# SparkFun_tDof-TMF8820.net
KiCad netlist of a schematic drawn in EAGLE
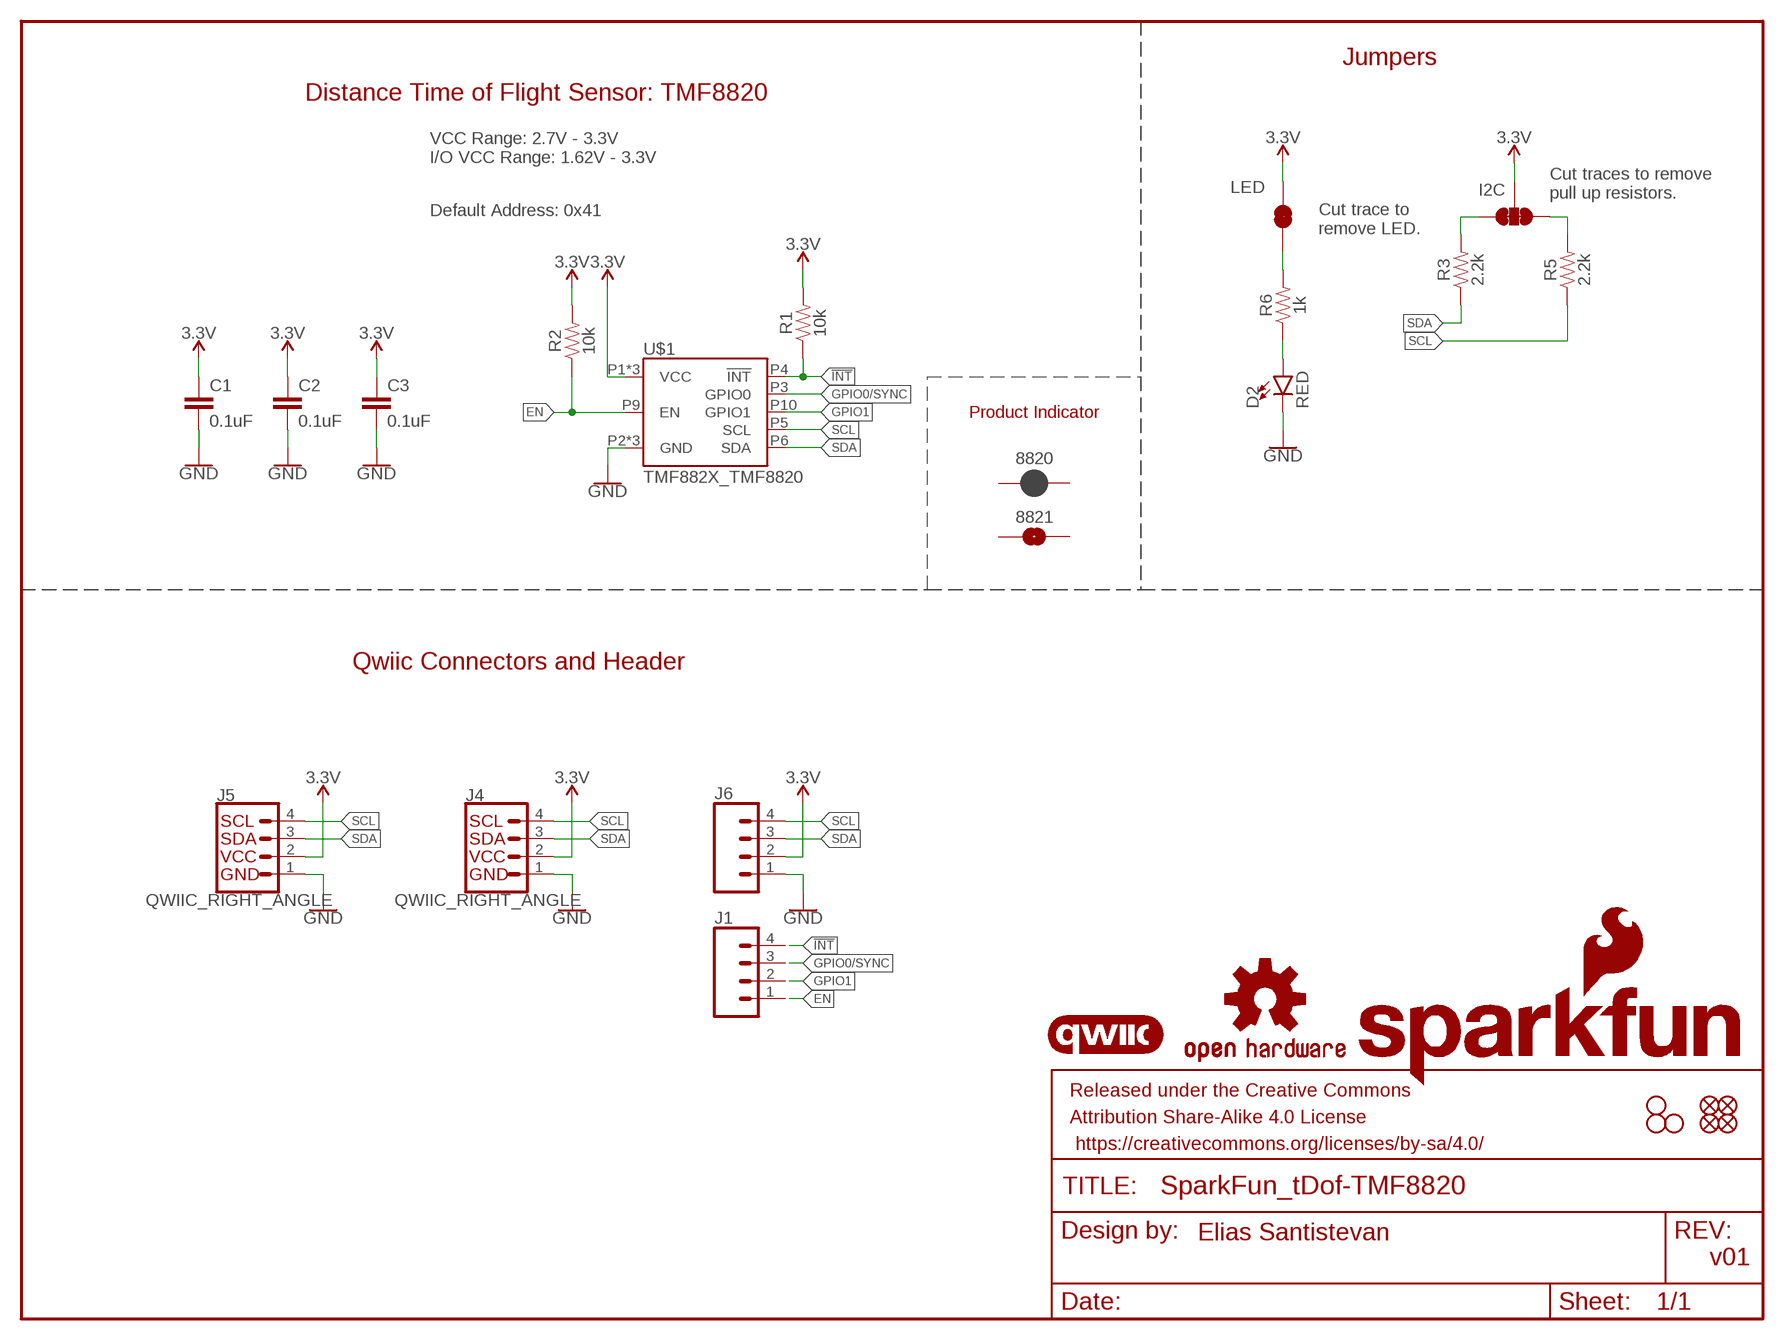
[diagram p0: schematic, sheet 1]

(export (version "E")
  (design (tool "Eeschema 10.0.6"))
  (components
    (comp (ref "8820")
      (value "JUMPER-SMT_2_NC_PASTE_SILK")
      (footprint "eagle-import:SMT-JUMPER_2_NC_PASTE_SILK")
      (libsource (lib "eagle-import") (part "JUMPER-SMT_2_NC_PASTE_SILK"))
    )
    (comp (ref "8821")
      (value "JUMPER-SMT_2_NO_SILK")
      (footprint "eagle-import:SMT-JUMPER_2_NO_SILK")
      (libsource (lib "eagle-import") (part "JUMPER-SMT_2_NO_SILK"))
    )
    (comp (ref "C1")
      (value "0.1uF")
      (footprint "eagle-import:0402-TIGHT")
      (libsource (lib "eagle-import") (part "0.1UF-0402T-6.3V-10%-X7R"))
    )
    (comp (ref "C2")
      (value "0.1uF")
      (footprint "eagle-import:0402-TIGHT")
      (libsource (lib "eagle-import") (part "0.1UF-0402T-6.3V-10%-X7R"))
    )
    (comp (ref "C3")
      (value "0.1uF")
      (footprint "eagle-import:0402-TIGHT")
      (libsource (lib "eagle-import") (part "0.1UF-0402T-6.3V-10%-X7R"))
    )
    (comp (ref "D2")
      (value "RED")
      (footprint "eagle-import:LED-0603")
      (libsource (lib "eagle-import") (part "LED-RED0603"))
    )
    (comp (ref "FD5")
      (value "FIDUCIALUFIDUCIAL")
      (footprint "eagle-import:FIDUCIAL-MICRO")
      (libsource (lib "eagle-import") (part "FIDUCIALUFIDUCIAL"))
    )
    (comp (ref "FD6")
      (value "FIDUCIALUFIDUCIAL")
      (footprint "eagle-import:FIDUCIAL-MICRO")
      (libsource (lib "eagle-import") (part "FIDUCIALUFIDUCIAL"))
    )
    (comp (ref "FD7")
      (value "FIDUCIALUFIDUCIAL")
      (footprint "eagle-import:FIDUCIAL-MICRO")
      (libsource (lib "eagle-import") (part "FIDUCIALUFIDUCIAL"))
    )
    (comp (ref "FD8")
      (value "FIDUCIALUFIDUCIAL")
      (footprint "eagle-import:FIDUCIAL-MICRO")
      (libsource (lib "eagle-import") (part "FIDUCIALUFIDUCIAL"))
    )
    (comp (ref "FRAME2")
      (value "FRAME-LETTER")
      (footprint "eagle-import:CREATIVE_COMMONS")
      (libsource (lib "eagle-import") (part "FRAME-LETTER"))
    )
    (comp (ref "H5")
      (value "STAND-OFFTIGHT")
      (footprint "eagle-import:STAND-OFF-TIGHT")
      (libsource (lib "eagle-import") (part "STAND-OFFTIGHT"))
    )
    (comp (ref "H6")
      (value "STAND-OFFTIGHT")
      (footprint "eagle-import:STAND-OFF-TIGHT")
      (libsource (lib "eagle-import") (part "STAND-OFFTIGHT"))
    )
    (comp (ref "H8")
      (value "STAND-OFFTIGHT")
      (footprint "eagle-import:STAND-OFF-TIGHT")
      (libsource (lib "eagle-import") (part "STAND-OFFTIGHT"))
    )
    (comp (ref "I2C")
      (value "I2C_PU")
      (footprint "eagle-import:SMT-JUMPER_3_2-NC_TRACE_SILK")
      (libsource (lib "eagle-import") (part "JUMPER-SMT_3_2-NC_TRACE_SILK"))
    )
    (comp (ref "J1")
      (value "CONN_041X04_NO_SILK_NO_POP")
      (footprint "eagle-import:1X04_NO_SILK")
      (libsource (lib "eagle-import") (part "CONN_041X04_NO_SILK_NO_POP"))
    )
    (comp (ref "J4")
      (value "QWIIC_RIGHT_ANGLE")
      (footprint "eagle-import:JST04_1MM_RA")
      (libsource (lib "eagle-import") (part "QWIIC_CONNECTORJS-1MM"))
    )
    (comp (ref "J5")
      (value "QWIIC_RIGHT_ANGLE")
      (footprint "eagle-import:JST04_1MM_RA")
      (libsource (lib "eagle-import") (part "QWIIC_CONNECTORJS-1MM"))
    )
    (comp (ref "J6")
      (value "CONN_041X04_NO_SILK")
      (footprint "eagle-import:1X04_NO_SILK")
      (libsource (lib "eagle-import") (part "CONN_041X04_NO_SILK"))
    )
    (comp (ref "LED")
      (value "LED")
      (footprint "eagle-import:SMT-JUMPER_2_NC_TRACE_SILK")
      (libsource (lib "eagle-import") (part "JUMPER-SMT_2_NC_TRACE_SILK"))
    )
    (comp (ref "LOGO3")
      (value "SFE_LOGO_NAME_FLAME.1_INCH")
      (footprint "eagle-import:SFE_LOGO_NAME_FLAME_.1")
      (libsource (lib "eagle-import") (part "SFE_LOGO_NAME_FLAME.1_INCH"))
    )
    (comp (ref "LOGO4")
      (value "OSHW-LOGOS")
      (footprint "eagle-import:OSHW-LOGO-S")
      (libsource (lib "eagle-import") (part "OSHW-LOGOS"))
    )
    (comp (ref "R1")
      (value "10k")
      (footprint "eagle-import:0603")
      (libsource (lib "eagle-import") (part "10KOHM-0603-1/10W-1%"))
    )
    (comp (ref "R2")
      (value "10k")
      (footprint "eagle-import:0603")
      (libsource (lib "eagle-import") (part "10KOHM-0603-1/10W-1%"))
    )
    (comp (ref "R3")
      (value "2.2k")
      (footprint "eagle-import:0603")
      (libsource (lib "eagle-import") (part "2.2KOHM-0603-1/10W-1%"))
    )
    (comp (ref "R5")
      (value "2.2k")
      (footprint "eagle-import:0603")
      (libsource (lib "eagle-import") (part "2.2KOHM-0603-1/10W-1%"))
    )
    (comp (ref "R6")
      (value "1k")
      (footprint "eagle-import:0603")
      (libsource (lib "eagle-import") (part "1KOHM-0603-1/10W-1%"))
    )
    (comp (ref "U$1")
      (value "TMF882X_TMF8820")
      (footprint "eagle-import:TMF882X")
      (libsource (lib "eagle-import") (part "TMF882X_TMF8820"))
    )
    (comp (ref "U$6")
      (value "QWIIC_LOGO_5MM")
      (footprint "eagle-import:QWIIC_5MM")
      (libsource (lib "eagle-import") (part "QWIIC_LOGO_5MM"))
    )
  )
  (nets
    (net (code "1") (name "/~{INT}") (class "Default")
      (node (ref "J1") (pin "4") (pinfunction "4_4") (pintype "passive"))
      (node (ref "R1") (pin "1") (pinfunction "1_1") (pintype "passive"))
      (node (ref "U$1") (pin "P4") (pinfunction "~{INT}_P4") (pintype "bidirectional"))
    )
    (net (code "2") (name "3.3V") (class "Default")
      (node (ref "C1") (pin "1") (pinfunction "1_1") (pintype "passive"))
      (node (ref "C2") (pin "1") (pinfunction "1_1") (pintype "passive"))
      (node (ref "C3") (pin "1") (pinfunction "1_1") (pintype "passive"))
      (node (ref "I2C") (pin "2") (pinfunction "2_2") (pintype "passive"))
      (node (ref "J4") (pin "2") (pinfunction "2_2") (pintype "power_in"))
      (node (ref "J5") (pin "2") (pinfunction "2_2") (pintype "power_in"))
      (node (ref "J6") (pin "2") (pinfunction "2_2") (pintype "passive"))
      (node (ref "LED") (pin "2") (pinfunction "2_2") (pintype "passive"))
      (node (ref "R1") (pin "2") (pinfunction "2_2") (pintype "passive"))
      (node (ref "R2") (pin "2") (pinfunction "2_2") (pintype "passive"))
      (node (ref "U$1") (pin "P1") (pinfunction "VCC_P1") (pintype "power_in"))
      (node (ref "U$1") (pin "P12") (pinfunction "VCC_P12") (pintype "power_in"))
      (node (ref "U$1") (pin "P7") (pinfunction "VCC_P7") (pintype "power_in"))
    )
    (net (code "3") (name "EN") (class "Default")
      (node (ref "J1") (pin "1") (pinfunction "1_1") (pintype "passive"))
      (node (ref "R2") (pin "1") (pinfunction "1_1") (pintype "passive"))
      (node (ref "U$1") (pin "P9") (pinfunction "EN_P9") (pintype "input"))
    )
    (net (code "4") (name "GND") (class "Default")
      (node (ref "C1") (pin "2") (pinfunction "2_2") (pintype "passive"))
      (node (ref "C2") (pin "2") (pinfunction "2_2") (pintype "passive"))
      (node (ref "C3") (pin "2") (pinfunction "2_2") (pintype "passive"))
      (node (ref "D2") (pin "C") (pinfunction "C_C") (pintype "passive"))
      (node (ref "J4") (pin "1") (pinfunction "1_1") (pintype "power_in"))
      (node (ref "J5") (pin "1") (pinfunction "1_1") (pintype "power_in"))
      (node (ref "J6") (pin "1") (pinfunction "1_1") (pintype "passive"))
      (node (ref "U$1") (pin "P11") (pinfunction "GND_P11") (pintype "power_in"))
      (node (ref "U$1") (pin "P2") (pinfunction "GND_P2") (pintype "power_in"))
      (node (ref "U$1") (pin "P8") (pinfunction "GND_P8") (pintype "power_in"))
    )
    (net (code "5") (name "GPIO0{slash}SYNC") (class "Default")
      (node (ref "J1") (pin "3") (pinfunction "3_3") (pintype "passive"))
      (node (ref "U$1") (pin "P3") (pinfunction "GPIO0_P3") (pintype "bidirectional"))
    )
    (net (code "6") (name "GPIO1") (class "Default")
      (node (ref "J1") (pin "2") (pinfunction "2_2") (pintype "passive"))
      (node (ref "U$1") (pin "P10") (pinfunction "GPIO1_P10") (pintype "bidirectional"))
    )
    (net (code "7") (name "Net-(D2-PadA)") (class "Default")
      (node (ref "D2") (pin "A") (pinfunction "A_A") (pintype "passive"))
      (node (ref "R6") (pin "1") (pinfunction "1_1") (pintype "passive"))
    )
    (net (code "8") (name "Net-(I2C-Pad1)") (class "Default")
      (node (ref "I2C") (pin "1") (pinfunction "1_1") (pintype "passive"))
      (node (ref "R5") (pin "2") (pinfunction "2_2") (pintype "passive"))
    )
    (net (code "9") (name "Net-(I2C-Pad3)") (class "Default")
      (node (ref "I2C") (pin "3") (pinfunction "3_3") (pintype "passive"))
      (node (ref "R3") (pin "2") (pinfunction "2_2") (pintype "passive"))
    )
    (net (code "10") (name "Net-(LED-Pad1)") (class "Default")
      (node (ref "LED") (pin "1") (pinfunction "1_1") (pintype "passive"))
      (node (ref "R6") (pin "2") (pinfunction "2_2") (pintype "passive"))
    )
    (net (code "11") (name "SCL") (class "Default")
      (node (ref "J4") (pin "4") (pinfunction "4_4") (pintype "passive"))
      (node (ref "J5") (pin "4") (pinfunction "4_4") (pintype "passive"))
      (node (ref "J6") (pin "4") (pinfunction "4_4") (pintype "passive"))
      (node (ref "R5") (pin "1") (pinfunction "1_1") (pintype "passive"))
      (node (ref "U$1") (pin "P5") (pinfunction "SCL_P5") (pintype "bidirectional"))
    )
    (net (code "12") (name "SDA") (class "Default")
      (node (ref "J4") (pin "3") (pinfunction "3_3") (pintype "passive"))
      (node (ref "J5") (pin "3") (pinfunction "3_3") (pintype "passive"))
      (node (ref "J6") (pin "3") (pinfunction "3_3") (pintype "passive"))
      (node (ref "R3") (pin "1") (pinfunction "1_1") (pintype "passive"))
      (node (ref "U$1") (pin "P6") (pinfunction "SDA_P6") (pintype "bidirectional"))
    )
    (net (code "13") (name "unconnected-(8820-Pad1)") (class "Default")
      (node (ref "8820") (pin "1") (pinfunction "1_1") (pintype "passive"))
    )
    (net (code "14") (name "unconnected-(8820-Pad2)") (class "Default")
      (node (ref "8820") (pin "2") (pinfunction "2_2") (pintype "passive"))
    )
    (net (code "15") (name "unconnected-(8821-Pad1)") (class "Default")
      (node (ref "8821") (pin "1") (pinfunction "1_1") (pintype "passive"))
    )
    (net (code "16") (name "unconnected-(8821-Pad2)") (class "Default")
      (node (ref "8821") (pin "2") (pinfunction "2_2") (pintype "passive"))
    )
  )
)
